# motor_shield.net
KiCad netlist of a schematic drawn in EAGLE
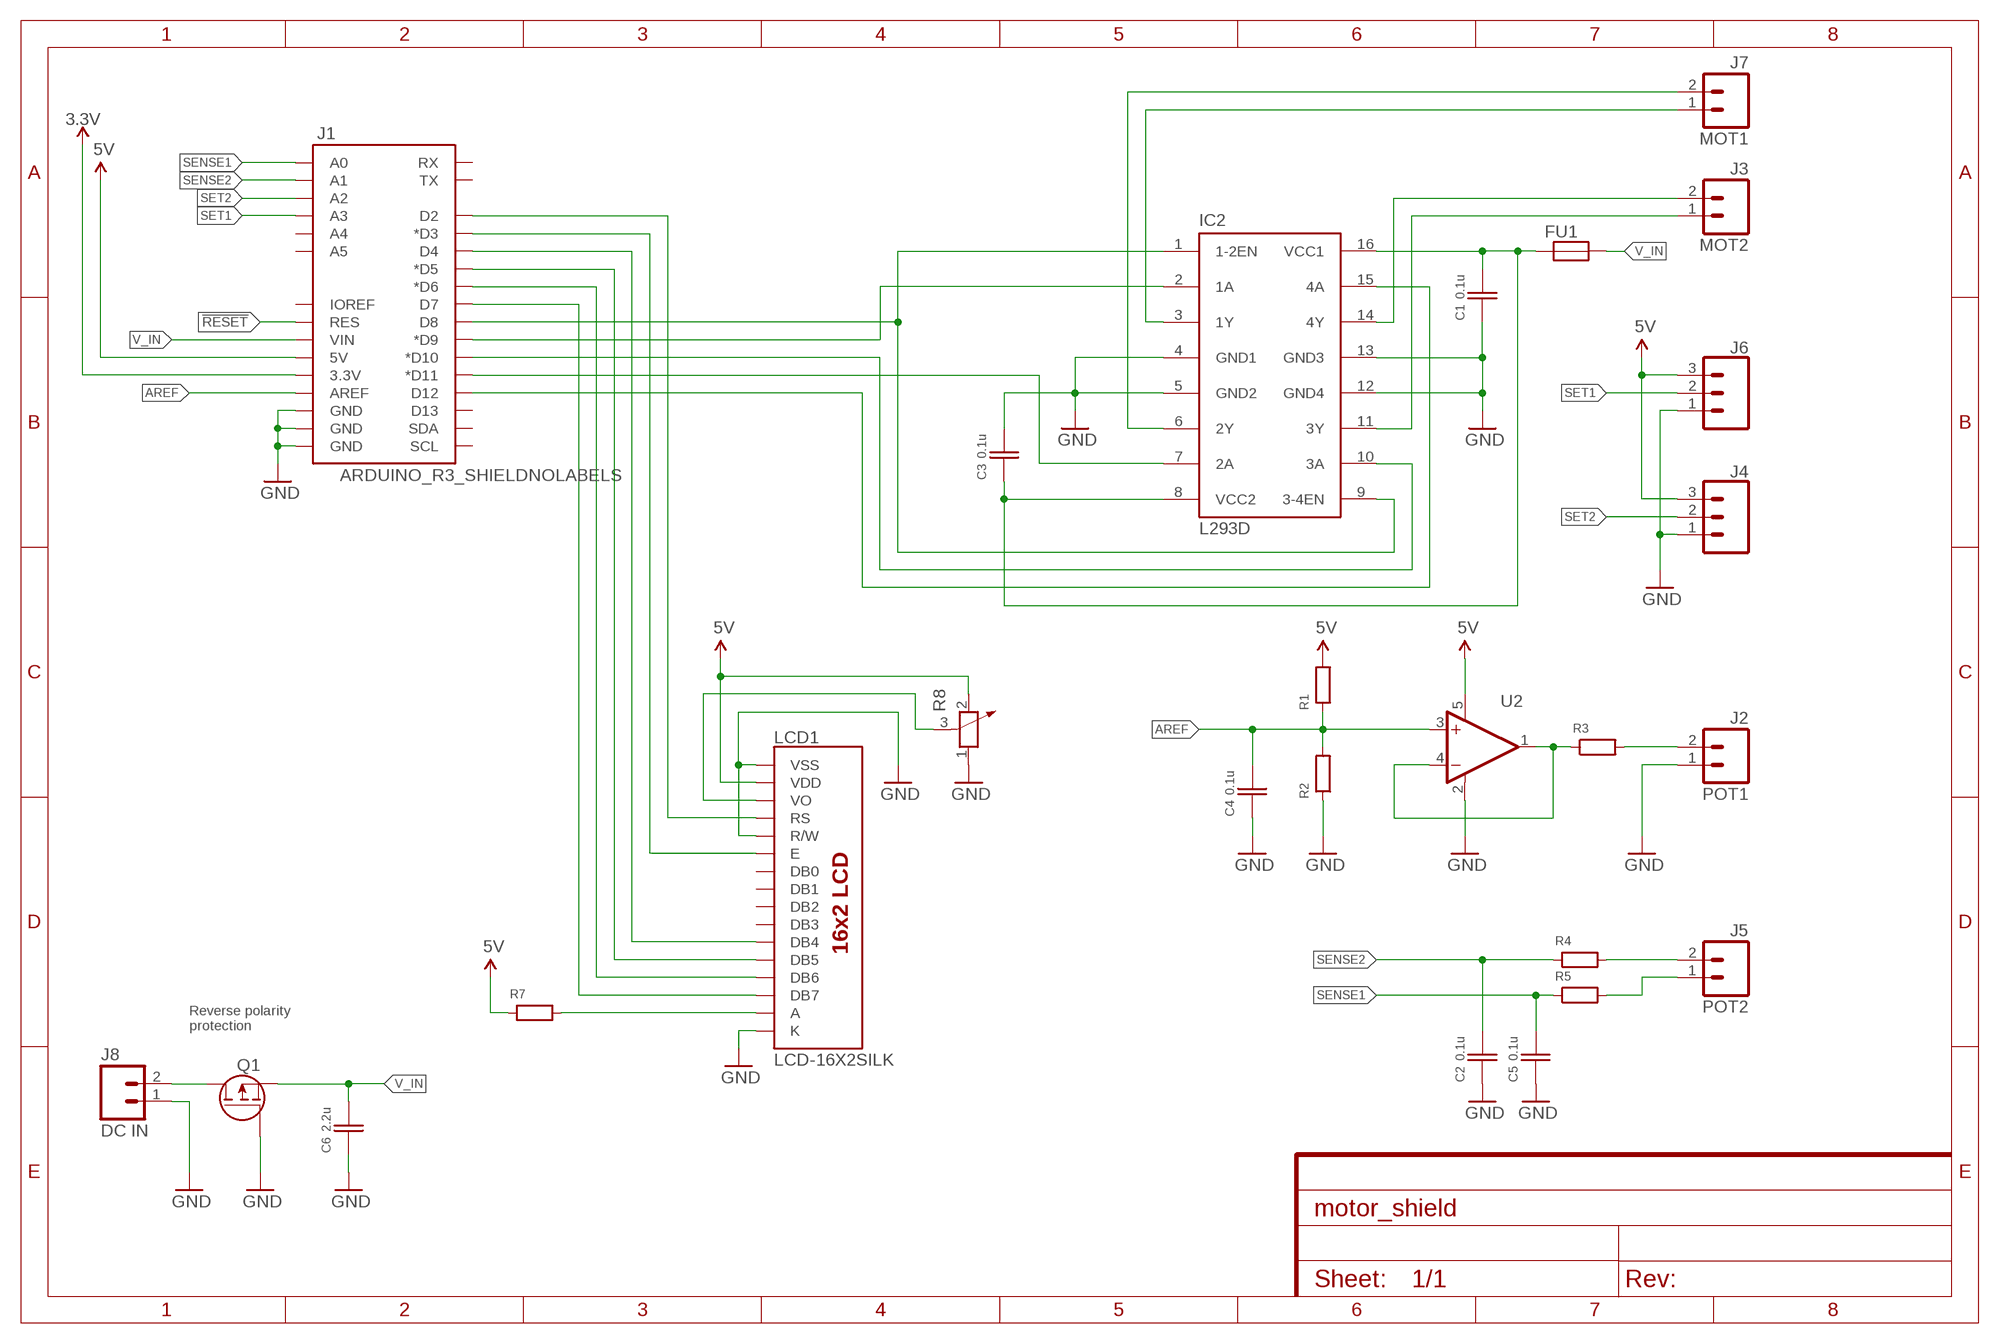
[diagram p0: schematic, sheet 1]

(export (version "E")
  (design (tool "Eeschema 10.0.6"))
  (components
    (comp (ref "C1")
      (value "0.1u")
      (footprint "eagle-import:C805")
      (libsource (lib "eagle-import") (part "CAPACITOR_NPOL-0805"))
    )
    (comp (ref "C2")
      (value "0.1u")
      (footprint "eagle-import:C603")
      (libsource (lib "eagle-import") (part "CAPACITOR_NPOL-0603"))
    )
    (comp (ref "C3")
      (value "0.1u")
      (footprint "eagle-import:C805")
      (libsource (lib "eagle-import") (part "CAPACITOR_NPOL-0805"))
    )
    (comp (ref "C4")
      (value "0.1u")
      (footprint "eagle-import:C603")
      (libsource (lib "eagle-import") (part "CAPACITOR_NPOL-0603"))
    )
    (comp (ref "C5")
      (value "0.1u")
      (footprint "eagle-import:C603")
      (libsource (lib "eagle-import") (part "CAPACITOR_NPOL-0603"))
    )
    (comp (ref "C6")
      (value "2.2u")
      (footprint "eagle-import:C1206")
      (libsource (lib "eagle-import") (part "CAPACITOR_NPOL-1206"))
    )
    (comp (ref "FU1")
      (value "PTC_FUSE")
      (footprint "eagle-import:C1812K")
      (libsource (lib "eagle-import") (part "PTC_FUSE"))
    )
    (comp (ref "IC2")
      (value "L293D")
      (footprint "eagle-import:DIL16")
      (libsource (lib "eagle-import") (part "L293D"))
    )
    (comp (ref "J1")
      (value "ARDUINO_R3_SHIELDNOLABELS")
      (footprint "eagle-import:UNO_R3_SHIELD_NOLABELS")
      (libsource (lib "eagle-import") (part "ARDUINO_R3_SHIELDNOLABELS"))
    )
    (comp (ref "J2")
      (value "POT1")
      (footprint "eagle-import:SCREWTERMINAL-3.5MM-2")
      (libsource (lib "eagle-import") (part "M023.5MM"))
    )
    (comp (ref "J3")
      (value "MOT2")
      (footprint "eagle-import:SCREWTERMINAL-3.5MM-2")
      (libsource (lib "eagle-import") (part "M023.5MM"))
    )
    (comp (ref "J4")
      (value "CONN_03SCREW")
      (footprint "eagle-import:SCREWTERMINAL-3.5MM-3")
      (libsource (lib "eagle-import") (part "CONN_03SCREW"))
    )
    (comp (ref "J5")
      (value "POT2")
      (footprint "eagle-import:SCREWTERMINAL-3.5MM-2")
      (libsource (lib "eagle-import") (part "M023.5MM"))
    )
    (comp (ref "J6")
      (value "CONN_03SCREW")
      (footprint "eagle-import:SCREWTERMINAL-3.5MM-3")
      (libsource (lib "eagle-import") (part "CONN_03SCREW"))
    )
    (comp (ref "J7")
      (value "MOT1")
      (footprint "eagle-import:SCREWTERMINAL-3.5MM-2")
      (libsource (lib "eagle-import") (part "M023.5MM"))
    )
    (comp (ref "J8")
      (value "DC IN")
      (footprint "eagle-import:SCREWTERMINAL-3.5MM-2")
      (libsource (lib "eagle-import") (part "M023.5MM"))
    )
    (comp (ref "LCD1")
      (value "LCD-16X2SILK")
      (footprint "eagle-import:LCD-16X2")
      (libsource (lib "eagle-import") (part "LCD-16X2SILK"))
    )
    (comp (ref "Q1")
      (value "MOSFET-P-SOT23-3")
      (footprint "eagle-import:SOT23-3")
      (libsource (lib "eagle-import") (part "MOSFET-P-SOT23-3"))
    )
    (comp (ref "R1")
      (value "RESISTOR-0603")
      (footprint "eagle-import:R0603")
      (libsource (lib "eagle-import") (part "RESISTOR-0603"))
    )
    (comp (ref "R2")
      (value "RESISTOR-0603")
      (footprint "eagle-import:R0603")
      (libsource (lib "eagle-import") (part "RESISTOR-0603"))
    )
    (comp (ref "R3")
      (value "RESISTOR-0603")
      (footprint "eagle-import:R0603")
      (libsource (lib "eagle-import") (part "RESISTOR-0603"))
    )
    (comp (ref "R4")
      (value "RESISTOR-0603")
      (footprint "eagle-import:R0603")
      (libsource (lib "eagle-import") (part "RESISTOR-0603"))
    )
    (comp (ref "R5")
      (value "RESISTOR-0603")
      (footprint "eagle-import:R0603")
      (libsource (lib "eagle-import") (part "RESISTOR-0603"))
    )
    (comp (ref "R7")
      (value "RESISTOR-0603")
      (footprint "eagle-import:R0603")
      (libsource (lib "eagle-import") (part "RESISTOR-0603"))
    )
    (comp (ref "R8")
      (value "POTENTIOMETER_PT-10S")
      (footprint "eagle-import:PT-10S")
      (libsource (lib "eagle-import") (part "POTENTIOMETER_PT-10S"))
    )
    (comp (ref "U2")
      (value "OPAMP-1CH-SOT23-5")
      (footprint "eagle-import:SOT23-5")
      (libsource (lib "eagle-import") (part "OPAMP-1CH-SOT23-5"))
    )
  )
  (nets
    (net (code "1") (name "/~{RESET}") (class "Default")
      (node (ref "J1") (pin "RES") (pinfunction "RES_RES") (pintype "bidirectional"))
    )
    (net (code "2") (name "3.3V") (class "Default")
      (node (ref "J1") (pin "3.3V") (pinfunction "3.3V_3.3V") (pintype "bidirectional"))
    )
    (net (code "3") (name "5V") (class "Default")
      (node (ref "J1") (pin "5V") (pinfunction "5V_5V") (pintype "bidirectional"))
      (node (ref "J4") (pin "3") (pinfunction "3_3") (pintype "passive"))
      (node (ref "J6") (pin "3") (pinfunction "3_3") (pintype "passive"))
      (node (ref "LCD1") (pin "2") (pinfunction "VDD_2") (pintype "power_in"))
      (node (ref "R1") (pin "2") (pinfunction "2_2") (pintype "passive"))
      (node (ref "R7") (pin "1") (pinfunction "1_1") (pintype "passive"))
      (node (ref "R8") (pin "2") (pinfunction "2_2") (pintype "passive"))
      (node (ref "U2") (pin "5") (pinfunction "V+_5") (pintype "power_in"))
    )
    (net (code "4") (name "AREF") (class "Default")
      (node (ref "C4") (pin "2") (pinfunction "2_2") (pintype "passive"))
      (node (ref "J1") (pin "AREF") (pinfunction "AREF_AREF") (pintype "bidirectional"))
      (node (ref "R1") (pin "1") (pinfunction "1_1") (pintype "passive"))
      (node (ref "R2") (pin "2") (pinfunction "2_2") (pintype "passive"))
      (node (ref "U2") (pin "3") (pinfunction "+IN_3") (pintype "input"))
    )
    (net (code "5") (name "GND") (class "Default")
      (node (ref "C1") (pin "1") (pinfunction "1_1") (pintype "passive"))
      (node (ref "C2") (pin "1") (pinfunction "1_1") (pintype "passive"))
      (node (ref "C3") (pin "2") (pinfunction "2_2") (pintype "passive"))
      (node (ref "C4") (pin "1") (pinfunction "1_1") (pintype "passive"))
      (node (ref "C5") (pin "1") (pinfunction "1_1") (pintype "passive"))
      (node (ref "C6") (pin "1") (pinfunction "1_1") (pintype "passive"))
      (node (ref "IC2") (pin "12") (pinfunction "GND4_12") (pintype "power_in"))
      (node (ref "IC2") (pin "13") (pinfunction "GND3_13") (pintype "power_in"))
      (node (ref "IC2") (pin "4") (pinfunction "GND1_4") (pintype "power_in"))
      (node (ref "IC2") (pin "5") (pinfunction "GND2_5") (pintype "power_in"))
      (node (ref "J1") (pin "GND@0") (pinfunction "GND_GND@0") (pintype "bidirectional"))
      (node (ref "J1") (pin "GND@1") (pinfunction "GND_GND@1") (pintype "bidirectional"))
      (node (ref "J1") (pin "GND@2") (pinfunction "GND_GND@2") (pintype "bidirectional"))
      (node (ref "J2") (pin "1") (pinfunction "1_1") (pintype "passive"))
      (node (ref "J4") (pin "1") (pinfunction "1_1") (pintype "passive"))
      (node (ref "J6") (pin "1") (pinfunction "1_1") (pintype "passive"))
      (node (ref "J8") (pin "1") (pinfunction "1_1") (pintype "passive"))
      (node (ref "LCD1") (pin "1") (pinfunction "VSS_1") (pintype "power_in"))
      (node (ref "LCD1") (pin "16") (pinfunction "K_16") (pintype "power_in"))
      (node (ref "LCD1") (pin "5") (pinfunction "R/W_5") (pintype "input"))
      (node (ref "Q1") (pin "1") (pinfunction "G_1") (pintype "passive"))
      (node (ref "R2") (pin "1") (pinfunction "1_1") (pintype "passive"))
      (node (ref "R8") (pin "1") (pinfunction "1_1") (pintype "passive"))
      (node (ref "U2") (pin "2") (pinfunction "V-_2") (pintype "power_in"))
    )
    (net (code "6") (name "Net-(IC2-1-2EN)") (class "Default")
      (node (ref "IC2") (pin "1") (pinfunction "1-2EN_1") (pintype "input"))
      (node (ref "IC2") (pin "9") (pinfunction "3-4EN_9") (pintype "input"))
      (node (ref "J1") (pin "D8") (pinfunction "D8_D8") (pintype "bidirectional"))
    )
    (net (code "7") (name "Net-(IC2-1A)") (class "Default")
      (node (ref "IC2") (pin "2") (pinfunction "1A_2") (pintype "input"))
      (node (ref "J1") (pin "D9") (pinfunction "*D9_D9") (pintype "bidirectional"))
    )
    (net (code "8") (name "Net-(IC2-1Y)") (class "Default")
      (node (ref "IC2") (pin "3") (pinfunction "1Y_3") (pintype "output"))
      (node (ref "J7") (pin "1") (pinfunction "1_1") (pintype "passive"))
    )
    (net (code "9") (name "Net-(IC2-2A)") (class "Default")
      (node (ref "IC2") (pin "7") (pinfunction "2A_7") (pintype "input"))
      (node (ref "J1") (pin "D11") (pinfunction "*D11_D11") (pintype "bidirectional"))
    )
    (net (code "10") (name "Net-(IC2-2Y)") (class "Default")
      (node (ref "IC2") (pin "6") (pinfunction "2Y_6") (pintype "output"))
      (node (ref "J7") (pin "2") (pinfunction "2_2") (pintype "passive"))
    )
    (net (code "11") (name "Net-(IC2-3A)") (class "Default")
      (node (ref "IC2") (pin "10") (pinfunction "3A_10") (pintype "input"))
      (node (ref "J1") (pin "D10") (pinfunction "*D10_D10") (pintype "bidirectional"))
    )
    (net (code "12") (name "Net-(IC2-3Y)") (class "Default")
      (node (ref "IC2") (pin "11") (pinfunction "3Y_11") (pintype "output"))
      (node (ref "J3") (pin "1") (pinfunction "1_1") (pintype "passive"))
    )
    (net (code "13") (name "Net-(IC2-4A)") (class "Default")
      (node (ref "IC2") (pin "15") (pinfunction "4A_15") (pintype "input"))
      (node (ref "J1") (pin "D12") (pinfunction "D12_D12") (pintype "bidirectional"))
    )
    (net (code "14") (name "Net-(IC2-4Y)") (class "Default")
      (node (ref "IC2") (pin "14") (pinfunction "4Y_14") (pintype "output"))
      (node (ref "J3") (pin "2") (pinfunction "2_2") (pintype "passive"))
    )
    (net (code "15") (name "Net-(IC2-VCC1)") (class "Default")
      (node (ref "C1") (pin "2") (pinfunction "2_2") (pintype "passive"))
      (node (ref "C3") (pin "1") (pinfunction "1_1") (pintype "passive"))
      (node (ref "FU1") (pin "1") (pinfunction "1_1") (pintype "passive"))
      (node (ref "IC2") (pin "16") (pinfunction "VCC1_16") (pintype "power_in"))
      (node (ref "IC2") (pin "8") (pinfunction "VCC2_8") (pintype "power_in"))
    )
    (net (code "16") (name "Net-(J1-*D3)") (class "Default")
      (node (ref "J1") (pin "D3") (pinfunction "*D3_D3") (pintype "bidirectional"))
      (node (ref "LCD1") (pin "6") (pinfunction "E_6") (pintype "input"))
    )
    (net (code "17") (name "Net-(J1-*D5)") (class "Default")
      (node (ref "J1") (pin "D5") (pinfunction "*D5_D5") (pintype "bidirectional"))
      (node (ref "LCD1") (pin "12") (pinfunction "DB5_12") (pintype "bidirectional"))
    )
    (net (code "18") (name "Net-(J1-*D6)") (class "Default")
      (node (ref "J1") (pin "D6") (pinfunction "*D6_D6") (pintype "bidirectional"))
      (node (ref "LCD1") (pin "13") (pinfunction "DB6_13") (pintype "bidirectional"))
    )
    (net (code "19") (name "Net-(J2-Pad2)") (class "Default")
      (node (ref "J2") (pin "2") (pinfunction "2_2") (pintype "passive"))
      (node (ref "R3") (pin "2") (pinfunction "2_2") (pintype "passive"))
    )
    (net (code "20") (name "Net-(J5-Pad1)") (class "Default")
      (node (ref "J5") (pin "1") (pinfunction "1_1") (pintype "passive"))
      (node (ref "R5") (pin "2") (pinfunction "2_2") (pintype "passive"))
    )
    (net (code "21") (name "Net-(J5-Pad2)") (class "Default")
      (node (ref "J5") (pin "2") (pinfunction "2_2") (pintype "passive"))
      (node (ref "R4") (pin "2") (pinfunction "2_2") (pintype "passive"))
    )
    (net (code "22") (name "Net-(LCD1-A)") (class "Default")
      (node (ref "LCD1") (pin "15") (pinfunction "A_15") (pintype "power_in"))
      (node (ref "R7") (pin "2") (pinfunction "2_2") (pintype "passive"))
    )
    (net (code "23") (name "Net-(LCD1-DB4)") (class "Default")
      (node (ref "J1") (pin "D4") (pinfunction "D4_D4") (pintype "bidirectional"))
      (node (ref "LCD1") (pin "11") (pinfunction "DB4_11") (pintype "bidirectional"))
    )
    (net (code "24") (name "Net-(LCD1-DB7)") (class "Default")
      (node (ref "J1") (pin "D7") (pinfunction "D7_D7") (pintype "bidirectional"))
      (node (ref "LCD1") (pin "14") (pinfunction "DB7_14") (pintype "bidirectional"))
    )
    (net (code "25") (name "Net-(LCD1-RS)") (class "Default")
      (node (ref "J1") (pin "D2") (pinfunction "D2_D2") (pintype "bidirectional"))
      (node (ref "LCD1") (pin "4") (pinfunction "RS_4") (pintype "input"))
    )
    (net (code "26") (name "Net-(LCD1-VO)") (class "Default")
      (node (ref "LCD1") (pin "3") (pinfunction "VO_3") (pintype "bidirectional"))
      (node (ref "R8") (pin "3") (pinfunction "3_3") (pintype "passive"))
    )
    (net (code "27") (name "Net-(Q1-D)") (class "Default")
      (node (ref "J8") (pin "2") (pinfunction "2_2") (pintype "passive"))
      (node (ref "Q1") (pin "3") (pinfunction "D_3") (pintype "passive"))
    )
    (net (code "28") (name "Net-(U2--IN)") (class "Default")
      (node (ref "R3") (pin "1") (pinfunction "1_1") (pintype "passive"))
      (node (ref "U2") (pin "1") (pinfunction "OUT_1") (pintype "output"))
      (node (ref "U2") (pin "4") (pinfunction "-IN_4") (pintype "input"))
    )
    (net (code "29") (name "SENSE1") (class "Default")
      (node (ref "C5") (pin "2") (pinfunction "2_2") (pintype "passive"))
      (node (ref "J1") (pin "A0") (pinfunction "A0_A0") (pintype "bidirectional"))
      (node (ref "R5") (pin "1") (pinfunction "1_1") (pintype "passive"))
    )
    (net (code "30") (name "SENSE2") (class "Default")
      (node (ref "C2") (pin "2") (pinfunction "2_2") (pintype "passive"))
      (node (ref "J1") (pin "A1") (pinfunction "A1_A1") (pintype "bidirectional"))
      (node (ref "R4") (pin "1") (pinfunction "1_1") (pintype "passive"))
    )
    (net (code "31") (name "SET1") (class "Default")
      (node (ref "J1") (pin "A3") (pinfunction "A3_A3") (pintype "bidirectional"))
      (node (ref "J6") (pin "2") (pinfunction "2_2") (pintype "passive"))
    )
    (net (code "32") (name "SET2") (class "Default")
      (node (ref "J1") (pin "A2") (pinfunction "A2_A2") (pintype "bidirectional"))
      (node (ref "J4") (pin "2") (pinfunction "2_2") (pintype "passive"))
    )
    (net (code "33") (name "V_IN") (class "Default")
      (node (ref "C6") (pin "2") (pinfunction "2_2") (pintype "passive"))
      (node (ref "FU1") (pin "2") (pinfunction "2_2") (pintype "passive"))
      (node (ref "J1") (pin "VIN") (pinfunction "VIN_VIN") (pintype "bidirectional"))
      (node (ref "Q1") (pin "2") (pinfunction "S_2") (pintype "passive"))
    )
    (net (code "34") (name "unconnected-(J1-PadA4)") (class "Default")
      (node (ref "J1") (pin "A4") (pinfunction "A4_A4") (pintype "bidirectional"))
    )
    (net (code "35") (name "unconnected-(J1-PadA5)") (class "Default")
      (node (ref "J1") (pin "A5") (pinfunction "A5_A5") (pintype "bidirectional"))
    )
    (net (code "36") (name "unconnected-(J1-PadD13)") (class "Default")
      (node (ref "J1") (pin "D13") (pinfunction "D13_D13") (pintype "bidirectional"))
    )
    (net (code "37") (name "unconnected-(J1-PadIOREF)") (class "Default")
      (node (ref "J1") (pin "IOREF") (pinfunction "IOREF_IOREF") (pintype "bidirectional"))
    )
    (net (code "38") (name "unconnected-(J1-PadRX)") (class "Default")
      (node (ref "J1") (pin "RX") (pinfunction "RX_RX") (pintype "bidirectional"))
    )
    (net (code "39") (name "unconnected-(J1-PadSCL)") (class "Default")
      (node (ref "J1") (pin "SCL") (pinfunction "SCL_SCL") (pintype "bidirectional"))
    )
    (net (code "40") (name "unconnected-(J1-PadSDA)") (class "Default")
      (node (ref "J1") (pin "SDA") (pinfunction "SDA_SDA") (pintype "bidirectional"))
    )
    (net (code "41") (name "unconnected-(J1-PadTX)") (class "Default")
      (node (ref "J1") (pin "TX") (pinfunction "TX_TX") (pintype "bidirectional"))
    )
    (net (code "42") (name "unconnected-(LCD1-DB0-Pad7)") (class "Default")
      (node (ref "LCD1") (pin "7") (pinfunction "DB0_7") (pintype "bidirectional"))
    )
    (net (code "43") (name "unconnected-(LCD1-DB1-Pad8)") (class "Default")
      (node (ref "LCD1") (pin "8") (pinfunction "DB1_8") (pintype "bidirectional"))
    )
    (net (code "44") (name "unconnected-(LCD1-DB2-Pad9)") (class "Default")
      (node (ref "LCD1") (pin "9") (pinfunction "DB2_9") (pintype "bidirectional"))
    )
    (net (code "45") (name "unconnected-(LCD1-DB3-Pad10)") (class "Default")
      (node (ref "LCD1") (pin "10") (pinfunction "DB3_10") (pintype "bidirectional"))
    )
  )
)
